# grab.net
KiCad netlist of a schematic drawn in EAGLE
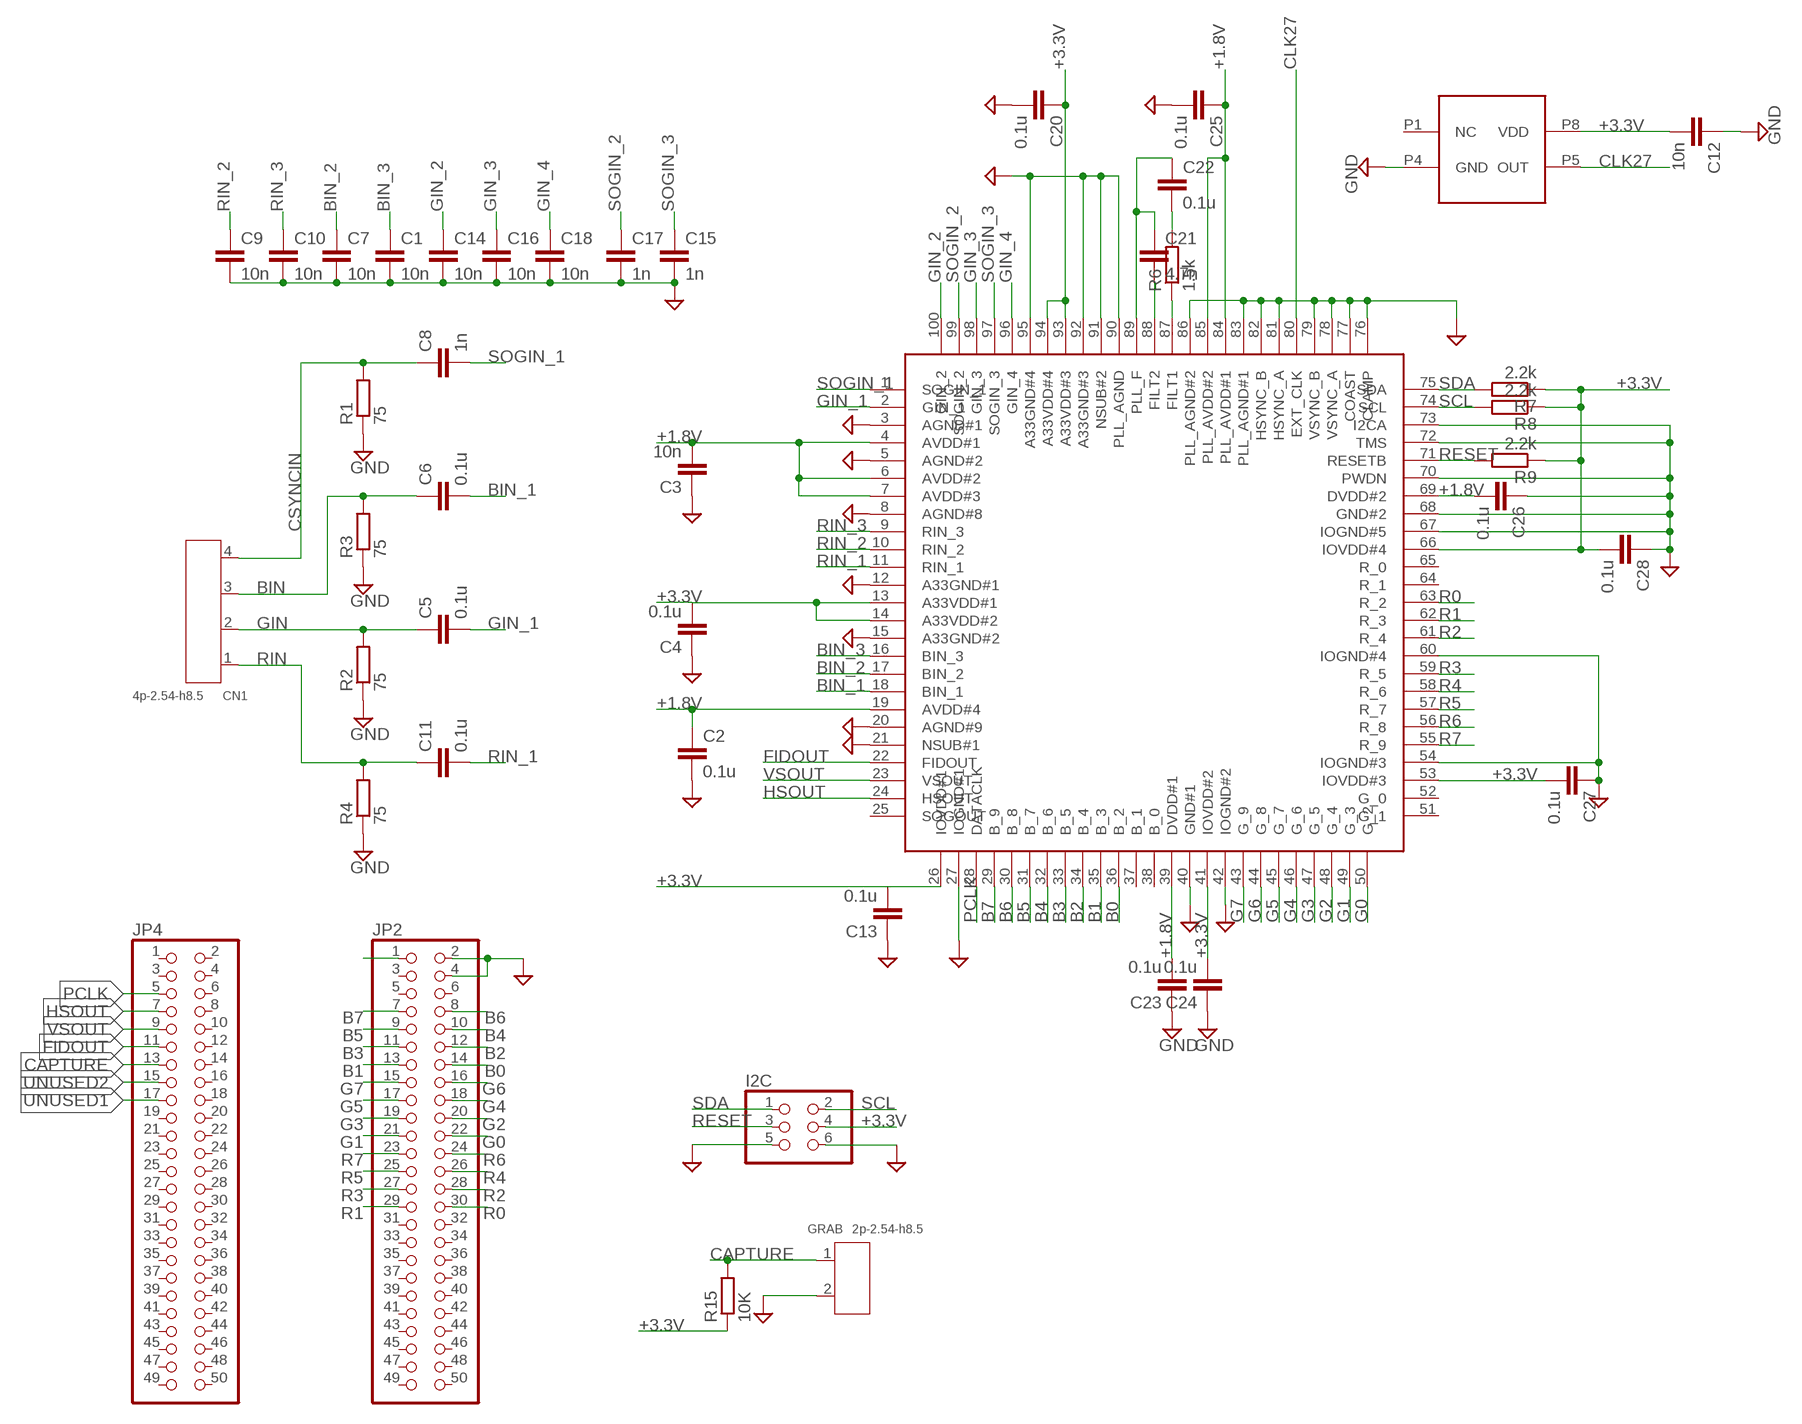
[diagram p0: schematic, sheet 1]
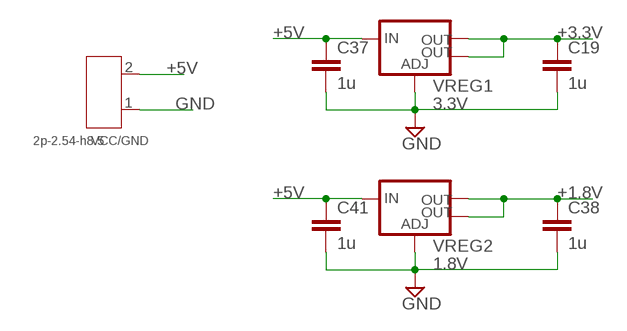
[diagram p1: schematic, sheet 2]
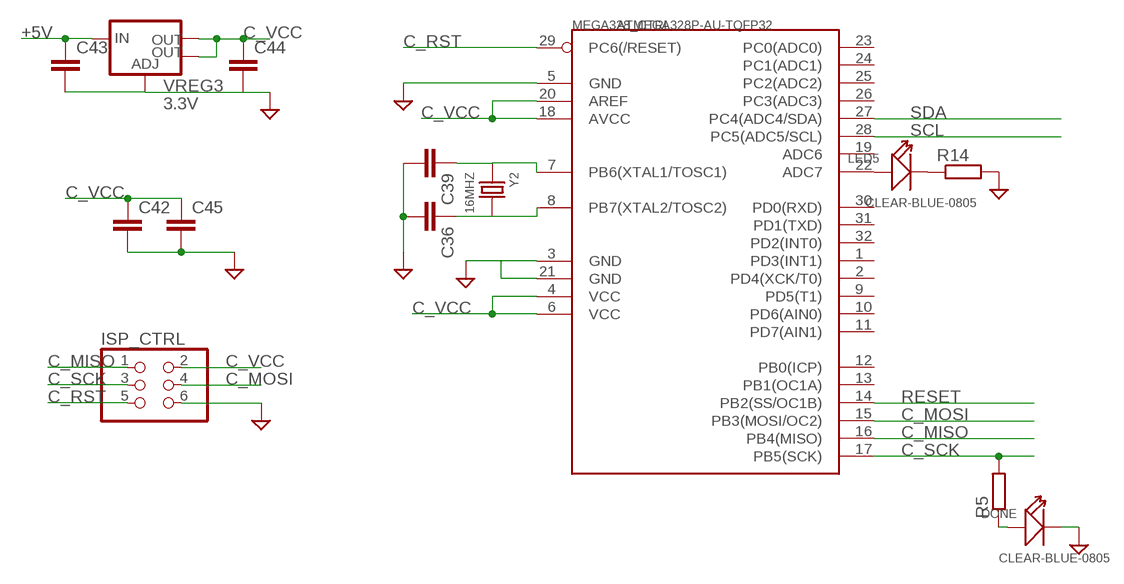
[diagram p2: schematic, sheet 3]
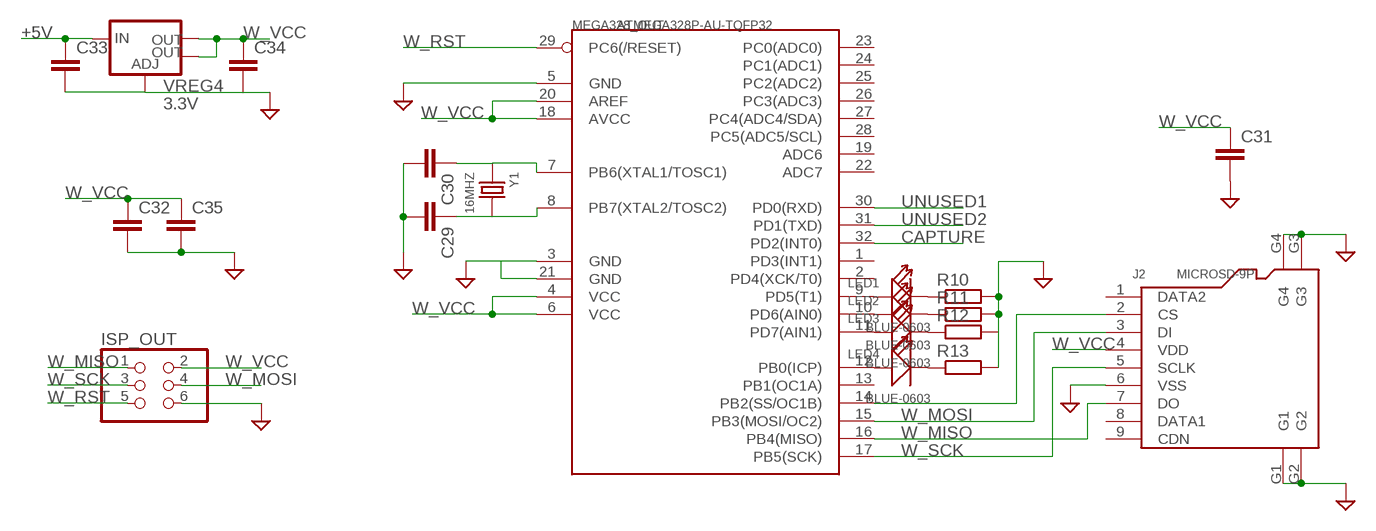
[diagram p3: schematic, sheet 4]

(export (version "E")
  (design (tool "Eeschema 10.0.6"))
  (components
    (comp (ref "C19")
      (value "1u")
      (footprint "eagle-import:C0603")
      (libsource (lib "eagle-import") (part "resistor_C-EUC0603"))
    )
    (comp (ref "C37")
      (value "1u")
      (footprint "eagle-import:C0603")
      (libsource (lib "eagle-import") (part "resistor_C-EUC0603"))
    )
    (comp (ref "C38")
      (value "1u")
      (footprint "eagle-import:C0603")
      (libsource (lib "eagle-import") (part "resistor_C-EUC0603"))
    )
    (comp (ref "C41")
      (value "1u")
      (footprint "eagle-import:C0603")
      (libsource (lib "eagle-import") (part "resistor_C-EUC0603"))
    )
    (comp (ref "VCC/GND")
      (value "2p-2.54-h8.5")
      (footprint "eagle-import:H2-2.54-3.44X6.3MM")
      (fields (field (name "MPN") "GS019-2.54-2P-1"))
      (libsource (lib "eagle-import") (part "DIP-SCREW-TERMINAL-GREEN(2P-2.54-H8.5)"))
    )
    (comp (ref "VREG1")
      (value "3.3V")
      (footprint "eagle-import:SOT223")
      (libsource (lib "eagle-import") (part "V_REG_LM1117SOT223"))
    )
    (comp (ref "VREG2")
      (value "1.8V")
      (footprint "eagle-import:SOT223")
      (libsource (lib "eagle-import") (part "V_REG_LM1117SOT223"))
    )
    (comp (ref "C36")
      (value "C-EUC0603")
      (footprint "eagle-import:C0603")
      (libsource (lib "eagle-import") (part "resistor_C-EUC0603"))
    )
    (comp (ref "C39")
      (value "C-EUC0603")
      (footprint "eagle-import:C0603")
      (libsource (lib "eagle-import") (part "resistor_C-EUC0603"))
    )
    (comp (ref "C42")
      (value "C-EUC0603")
      (footprint "eagle-import:C0603")
      (libsource (lib "eagle-import") (part "resistor_C-EUC0603"))
    )
    (comp (ref "C43")
      (value "C-EUC0603")
      (footprint "eagle-import:C0603")
      (libsource (lib "eagle-import") (part "resistor_C-EUC0603"))
    )
    (comp (ref "C44")
      (value "C-EUC0603")
      (footprint "eagle-import:C0603")
      (libsource (lib "eagle-import") (part "resistor_C-EUC0603"))
    )
    (comp (ref "C45")
      (value "C-EUC0603")
      (footprint "eagle-import:C0603")
      (libsource (lib "eagle-import") (part "resistor_C-EUC0603"))
    )
    (comp (ref "DONE")
      (value "CLEAR-BLUE-0805")
      (footprint "eagle-import:LED-0805")
      (fields (field (name "MPN") "EL-17-215/BHC-AN1P2/3T"))
      (libsource (lib "eagle-import") (part "SMD-LED-CLEAR-BLUE(0805)"))
    )
    (comp (ref "ISP_CTRL")
      (value "PINHD-2X3")
      (footprint "eagle-import:2X03")
      (libsource (lib "eagle-import") (part "PINHD-2X3"))
    )
    (comp (ref "LED5")
      (value "CLEAR-BLUE-0805")
      (footprint "eagle-import:LED-0805")
      (fields (field (name "MPN") "EL-17-215/BHC-AN1P2/3T"))
      (libsource (lib "eagle-import") (part "SMD-LED-CLEAR-BLUE(0805)"))
    )
    (comp (ref "MEGA328_CTRL")
      (value "ATMEGA328P-AU-TQFP32")
      (footprint "eagle-import:TQFP32-0.8-7X7MM")
      (fields (field (name "MPN") "ATMEGA328P-AU"))
      (libsource (lib "eagle-import") (part "MCU-ATMEGA328P-AU(TQFP32)"))
    )
    (comp (ref "R5")
      (value "R-EU_R0603")
      (footprint "eagle-import:R0603")
      (libsource (lib "eagle-import") (part "R-EU_R0603"))
    )
    (comp (ref "R14")
      (value "R-EU_R0603")
      (footprint "eagle-import:R0603")
      (libsource (lib "eagle-import") (part "R-EU_R0603"))
    )
    (comp (ref "VREG3")
      (value "3.3V")
      (footprint "eagle-import:SOT223")
      (libsource (lib "eagle-import") (part "V_REG_LM1117SOT223"))
    )
    (comp (ref "Y2")
      (value "16MHZ")
      (footprint "eagle-import:X2-SMD-5.0X3.2X1.3MM")
      (fields (field (name "MPN") "X053201602002"))
      (libsource (lib "eagle-import") (part "SMD-CRYSTAL-16MHZ-8PF-20PPM-40R(2P-5.0X3.2MM)"))
    )
    (comp (ref "C29")
      (value "C-EUC0603")
      (footprint "eagle-import:C0603")
      (libsource (lib "eagle-import") (part "resistor_C-EUC0603"))
    )
    (comp (ref "C30")
      (value "C-EUC0603")
      (footprint "eagle-import:C0603")
      (libsource (lib "eagle-import") (part "resistor_C-EUC0603"))
    )
    (comp (ref "C31")
      (value "C-EUC0603")
      (footprint "eagle-import:C0603")
      (libsource (lib "eagle-import") (part "resistor_C-EUC0603"))
    )
    (comp (ref "C32")
      (value "C-EUC0603")
      (footprint "eagle-import:C0603")
      (libsource (lib "eagle-import") (part "resistor_C-EUC0603"))
    )
    (comp (ref "C33")
      (value "C-EUC0603")
      (footprint "eagle-import:C0603")
      (libsource (lib "eagle-import") (part "resistor_C-EUC0603"))
    )
    (comp (ref "C34")
      (value "C-EUC0603")
      (footprint "eagle-import:C0603")
      (libsource (lib "eagle-import") (part "resistor_C-EUC0603"))
    )
    (comp (ref "C35")
      (value "C-EUC0603")
      (footprint "eagle-import:C0603")
      (libsource (lib "eagle-import") (part "resistor_C-EUC0603"))
    )
    (comp (ref "ISP_OUT")
      (value "PINHD-2X3")
      (footprint "eagle-import:2X03")
      (libsource (lib "eagle-import") (part "PINHD-2X3"))
    )
    (comp (ref "J2")
      (value "MICROSD-9P")
      (footprint "eagle-import:MICRO-SD9+4P-SMD-16.1X14.5X1.85MM")
      (libsource (lib "eagle-import") (part "MICRO-SD-CARD-HOLDER-9P"))
    )
    (comp (ref "LED1")
      (value "BLUE-0603")
      (footprint "eagle-import:LED-0603")
      (fields (field (name "MPN") "19-217-BHC-ZL1M2RY-3T"))
      (libsource (lib "eagle-import") (part "SMD-LED-CLEAR-BLUE(0603)"))
    )
    (comp (ref "LED2")
      (value "BLUE-0603")
      (footprint "eagle-import:LED-0603")
      (fields (field (name "MPN") "19-217-BHC-ZL1M2RY-3T"))
      (libsource (lib "eagle-import") (part "SMD-LED-CLEAR-BLUE(0603)"))
    )
    (comp (ref "LED3")
      (value "BLUE-0603")
      (footprint "eagle-import:LED-0603")
      (fields (field (name "MPN") "19-217-BHC-ZL1M2RY-3T"))
      (libsource (lib "eagle-import") (part "SMD-LED-CLEAR-BLUE(0603)"))
    )
    (comp (ref "LED4")
      (value "BLUE-0603")
      (footprint "eagle-import:LED-0603")
      (fields (field (name "MPN") "19-217-BHC-ZL1M2RY-3T"))
      (libsource (lib "eagle-import") (part "SMD-LED-CLEAR-BLUE(0603)"))
    )
    (comp (ref "MEGA328_OUT")
      (value "ATMEGA328P-AU-TQFP32")
      (footprint "eagle-import:TQFP32-0.8-7X7MM")
      (fields (field (name "MPN") "ATMEGA328P-AU"))
      (libsource (lib "eagle-import") (part "MCU-ATMEGA328P-AU(TQFP32)"))
    )
    (comp (ref "R10")
      (value "R-EU_R0603")
      (footprint "eagle-import:R0603")
      (libsource (lib "eagle-import") (part "R-EU_R0603"))
    )
    (comp (ref "R11")
      (value "R-EU_R0603")
      (footprint "eagle-import:R0603")
      (libsource (lib "eagle-import") (part "R-EU_R0603"))
    )
    (comp (ref "R12")
      (value "R-EU_R0603")
      (footprint "eagle-import:R0603")
      (libsource (lib "eagle-import") (part "R-EU_R0603"))
    )
    (comp (ref "R13")
      (value "R-EU_R0603")
      (footprint "eagle-import:R0603")
      (libsource (lib "eagle-import") (part "R-EU_R0603"))
    )
    (comp (ref "VREG4")
      (value "3.3V")
      (footprint "eagle-import:SOT223")
      (libsource (lib "eagle-import") (part "V_REG_LM1117SOT223"))
    )
    (comp (ref "Y1")
      (value "16MHZ")
      (footprint "eagle-import:X2-SMD-5.0X3.2X1.3MM")
      (fields (field (name "MPN") "X053201602002"))
      (libsource (lib "eagle-import") (part "SMD-CRYSTAL-16MHZ-8PF-20PPM-40R(2P-5.0X3.2MM)"))
    )
    (comp (ref "27MHZ")
      (value "ACHL-27MHZ-EK")
      (footprint "eagle-import:DIP4")
      (libsource (lib "eagle-import") (part "ACHL-27MHZ-EK"))
    )
    (comp (ref "C1")
      (value "10n")
      (footprint "eagle-import:C0603")
      (libsource (lib "eagle-import") (part "resistor_C-EUC0603"))
    )
    (comp (ref "C2")
      (value "0.1u")
      (footprint "eagle-import:C0603")
      (libsource (lib "eagle-import") (part "resistor_C-EUC0603"))
    )
    (comp (ref "C3")
      (value "10n")
      (footprint "eagle-import:C0603")
      (libsource (lib "eagle-import") (part "resistor_C-EUC0603"))
    )
    (comp (ref "C4")
      (value "0.1u")
      (footprint "eagle-import:C0603")
      (libsource (lib "eagle-import") (part "resistor_C-EUC0603"))
    )
    (comp (ref "C5")
      (value "0.1u")
      (footprint "eagle-import:C0603")
      (libsource (lib "eagle-import") (part "resistor_C-EUC0603"))
    )
    (comp (ref "C6")
      (value "0.1u")
      (footprint "eagle-import:C0603")
      (libsource (lib "eagle-import") (part "resistor_C-EUC0603"))
    )
    (comp (ref "C7")
      (value "10n")
      (footprint "eagle-import:C0603")
      (libsource (lib "eagle-import") (part "resistor_C-EUC0603"))
    )
    (comp (ref "C8")
      (value "1n")
      (footprint "eagle-import:C0603")
      (libsource (lib "eagle-import") (part "resistor_C-EUC0603"))
    )
    (comp (ref "C9")
      (value "10n")
      (footprint "eagle-import:C0603")
      (libsource (lib "eagle-import") (part "resistor_C-EUC0603"))
    )
    (comp (ref "C10")
      (value "10n")
      (footprint "eagle-import:C0603")
      (libsource (lib "eagle-import") (part "resistor_C-EUC0603"))
    )
    (comp (ref "C11")
      (value "0.1u")
      (footprint "eagle-import:C0603")
      (libsource (lib "eagle-import") (part "resistor_C-EUC0603"))
    )
    (comp (ref "C12")
      (value "10n")
      (footprint "eagle-import:C0805")
      (libsource (lib "eagle-import") (part "C-EUC0805"))
    )
    (comp (ref "C13")
      (value "0.1u")
      (footprint "eagle-import:C0603")
      (libsource (lib "eagle-import") (part "resistor_C-EUC0603"))
    )
    (comp (ref "C14")
      (value "10n")
      (footprint "eagle-import:C0603")
      (libsource (lib "eagle-import") (part "resistor_C-EUC0603"))
    )
    (comp (ref "C15")
      (value "1n")
      (footprint "eagle-import:C0603")
      (libsource (lib "eagle-import") (part "resistor_C-EUC0603"))
    )
    (comp (ref "C16")
      (value "10n")
      (footprint "eagle-import:C0603")
      (libsource (lib "eagle-import") (part "resistor_C-EUC0603"))
    )
    (comp (ref "C17")
      (value "1n")
      (footprint "eagle-import:C0603")
      (libsource (lib "eagle-import") (part "resistor_C-EUC0603"))
    )
    (comp (ref "C18")
      (value "10n")
      (footprint "eagle-import:C0603")
      (libsource (lib "eagle-import") (part "resistor_C-EUC0603"))
    )
    (comp (ref "C20")
      (value "0.1u")
      (footprint "eagle-import:C0603")
      (libsource (lib "eagle-import") (part "resistor_C-EUC0603"))
    )
    (comp (ref "C21")
      (value "4.7n")
      (footprint "eagle-import:C0603")
      (libsource (lib "eagle-import") (part "resistor_C-EUC0603"))
    )
    (comp (ref "C22")
      (value "0.1u")
      (footprint "eagle-import:C0603")
      (libsource (lib "eagle-import") (part "resistor_C-EUC0603"))
    )
    (comp (ref "C23")
      (value "0.1u")
      (footprint "eagle-import:C0603")
      (libsource (lib "eagle-import") (part "resistor_C-EUC0603"))
    )
    (comp (ref "C24")
      (value "0.1u")
      (footprint "eagle-import:C0603")
      (libsource (lib "eagle-import") (part "resistor_C-EUC0603"))
    )
    (comp (ref "C25")
      (value "0.1u")
      (footprint "eagle-import:C0603")
      (libsource (lib "eagle-import") (part "resistor_C-EUC0603"))
    )
    (comp (ref "C26")
      (value "0.1u")
      (footprint "eagle-import:C0603")
      (libsource (lib "eagle-import") (part "resistor_C-EUC0603"))
    )
    (comp (ref "C27")
      (value "0.1u")
      (footprint "eagle-import:C0603")
      (libsource (lib "eagle-import") (part "resistor_C-EUC0603"))
    )
    (comp (ref "C28")
      (value "0.1u")
      (footprint "eagle-import:C0603")
      (libsource (lib "eagle-import") (part "resistor_C-EUC0603"))
    )
    (comp (ref "CN1")
      (value "4p-2.54-h8.5")
      (footprint "eagle-import:H4-2.54-8.52X6.3MM")
      (fields (field (name "MPN") "GS019-2.54-4P-1"))
      (libsource (lib "eagle-import") (part "DIP-SCREW-TERMINAL-GREEN(4P-2.54-H8.5)"))
    )
    (comp (ref "GRAB")
      (value "2p-2.54-h8.5")
      (footprint "eagle-import:H2-2.54-3.44X6.3MM")
      (fields (field (name "MPN") "GS019-2.54-2P-1"))
      (libsource (lib "eagle-import") (part "DIP-SCREW-TERMINAL-GREEN(2P-2.54-H8.5)"))
    )
    (comp (ref "I2C")
      (value "PINHD-2X3")
      (footprint "eagle-import:2X03")
      (libsource (lib "eagle-import") (part "PINHD-2X3"))
    )
    (comp (ref "JP2")
      (value "PINHD-2X25")
      (footprint "eagle-import:2X25")
      (libsource (lib "eagle-import") (part "PINHD-2X25"))
    )
    (comp (ref "JP4")
      (value "PINHD-2X25")
      (footprint "eagle-import:2X25")
      (libsource (lib "eagle-import") (part "PINHD-2X25"))
    )
    (comp (ref "R1")
      (value "75")
      (footprint "eagle-import:R0603")
      (libsource (lib "eagle-import") (part "R-EU_R0603"))
    )
    (comp (ref "R2")
      (value "75")
      (footprint "eagle-import:R0603")
      (libsource (lib "eagle-import") (part "R-EU_R0603"))
    )
    (comp (ref "R3")
      (value "75")
      (footprint "eagle-import:R0603")
      (libsource (lib "eagle-import") (part "R-EU_R0603"))
    )
    (comp (ref "R4")
      (value "75")
      (footprint "eagle-import:R0603")
      (libsource (lib "eagle-import") (part "R-EU_R0603"))
    )
    (comp (ref "R6")
      (value "1.5k")
      (footprint "eagle-import:R0603")
      (libsource (lib "eagle-import") (part "R-EU_R0603"))
    )
    (comp (ref "R7")
      (value "2.2k")
      (footprint "eagle-import:R0603")
      (libsource (lib "eagle-import") (part "R-EU_R0603"))
    )
    (comp (ref "R8")
      (value "2.2k")
      (footprint "eagle-import:R0603")
      (libsource (lib "eagle-import") (part "R-EU_R0603"))
    )
    (comp (ref "R9")
      (value "2.2k")
      (footprint "eagle-import:R0603")
      (libsource (lib "eagle-import") (part "R-EU_R0603"))
    )
    (comp (ref "R15")
      (value "10K")
      (footprint "eagle-import:R0603")
      (libsource (lib "eagle-import") (part "R-EU_R0603"))
    )
    (comp (ref "TVP7002")
      (value "TVP7002")
      (footprint "eagle-import:TQFP100")
      (libsource (lib "eagle-import") (part "TVP7002"))
    )
  )
  (nets
    (net (code "1") (name "+1.8V") (class "Default")
      (node (ref "C2") (pin "1") (pinfunction "1_1") (pintype "passive"))
      (node (ref "C23") (pin "2") (pinfunction "2_2") (pintype "passive"))
      (node (ref "C25") (pin "1") (pinfunction "1_1") (pintype "passive"))
      (node (ref "C26") (pin "2") (pinfunction "2_2") (pintype "passive"))
      (node (ref "C3") (pin "2") (pinfunction "2_2") (pintype "passive"))
      (node (ref "C38") (pin "1") (pinfunction "1_1") (pintype "passive"))
      (node (ref "TVP7002") (pin "19") (pinfunction "AVDD#4_19") (pintype "bidirectional"))
      (node (ref "TVP7002") (pin "39") (pinfunction "DVDD#1_39") (pintype "bidirectional"))
      (node (ref "TVP7002") (pin "4") (pinfunction "AVDD#1_4") (pintype "bidirectional"))
      (node (ref "TVP7002") (pin "6") (pinfunction "AVDD#2_6") (pintype "bidirectional"))
      (node (ref "TVP7002") (pin "69") (pinfunction "DVDD#2_69") (pintype "bidirectional"))
      (node (ref "TVP7002") (pin "7") (pinfunction "AVDD#3_7") (pintype "bidirectional"))
      (node (ref "TVP7002") (pin "84") (pinfunction "PLL_AVDD#1_84") (pintype "bidirectional"))
      (node (ref "TVP7002") (pin "85") (pinfunction "PLL_AVDD#2_85") (pintype "bidirectional"))
      (node (ref "VREG2") (pin "2") (pinfunction "OUT_2") (pintype "output"))
      (node (ref "VREG2") (pin "4") (pinfunction "OUT_4") (pintype "output"))
    )
    (net (code "2") (name "+3.3V") (class "Default")
      (node (ref "27MHZ") (pin "P8") (pinfunction "VDD_P8") (pintype "bidirectional"))
      (node (ref "C12") (pin "2") (pinfunction "2_2") (pintype "passive"))
      (node (ref "C13") (pin "2") (pinfunction "2_2") (pintype "passive"))
      (node (ref "C19") (pin "1") (pinfunction "1_1") (pintype "passive"))
      (node (ref "C20") (pin "1") (pinfunction "1_1") (pintype "passive"))
      (node (ref "C24") (pin "2") (pinfunction "2_2") (pintype "passive"))
      (node (ref "C27") (pin "2") (pinfunction "2_2") (pintype "passive"))
      (node (ref "C28") (pin "2") (pinfunction "2_2") (pintype "passive"))
      (node (ref "C4") (pin "2") (pinfunction "2_2") (pintype "passive"))
      (node (ref "I2C") (pin "4") (pinfunction "4_4") (pintype "passive"))
      (node (ref "R15") (pin "1") (pinfunction "1_1") (pintype "passive"))
      (node (ref "R7") (pin "1") (pinfunction "1_1") (pintype "passive"))
      (node (ref "R8") (pin "1") (pinfunction "1_1") (pintype "passive"))
      (node (ref "R9") (pin "1") (pinfunction "1_1") (pintype "passive"))
      (node (ref "TVP7002") (pin "13") (pinfunction "A33VDD#1_13") (pintype "bidirectional"))
      (node (ref "TVP7002") (pin "14") (pinfunction "A33VDD#2_14") (pintype "bidirectional"))
      (node (ref "TVP7002") (pin "26") (pinfunction "IOVDD#1_26") (pintype "bidirectional"))
      (node (ref "TVP7002") (pin "41") (pinfunction "IOVDD#2_41") (pintype "bidirectional"))
      (node (ref "TVP7002") (pin "53") (pinfunction "IOVDD#3_53") (pintype "bidirectional"))
      (node (ref "TVP7002") (pin "66") (pinfunction "IOVDD#4_66") (pintype "bidirectional"))
      (node (ref "TVP7002") (pin "93") (pinfunction "A33VDD#3_93") (pintype "bidirectional"))
      (node (ref "TVP7002") (pin "94") (pinfunction "A33VDD#4_94") (pintype "bidirectional"))
      (node (ref "VREG1") (pin "2") (pinfunction "OUT_2") (pintype "output"))
      (node (ref "VREG1") (pin "4") (pinfunction "OUT_4") (pintype "output"))
    )
    (net (code "3") (name "+5V") (class "Default")
      (node (ref "C33") (pin "1") (pinfunction "1_1") (pintype "passive"))
      (node (ref "C37") (pin "1") (pinfunction "1_1") (pintype "passive"))
      (node (ref "C41") (pin "1") (pinfunction "1_1") (pintype "passive"))
      (node (ref "C43") (pin "1") (pinfunction "1_1") (pintype "passive"))
      (node (ref "VCC/GND") (pin "2") (pinfunction "2_2") (pintype "bidirectional"))
      (node (ref "VREG1") (pin "3") (pinfunction "IN_3") (pintype "input"))
      (node (ref "VREG2") (pin "3") (pinfunction "IN_3") (pintype "input"))
      (node (ref "VREG3") (pin "3") (pinfunction "IN_3") (pintype "input"))
      (node (ref "VREG4") (pin "3") (pinfunction "IN_3") (pintype "input"))
    )
    (net (code "4") (name "B0") (class "Default")
      (node (ref "JP2") (pin "14") (pinfunction "14_14") (pintype "passive"))
      (node (ref "TVP7002") (pin "36") (pinfunction "B_2_36") (pintype "bidirectional"))
    )
    (net (code "5") (name "B1") (class "Default")
      (node (ref "JP2") (pin "13") (pinfunction "13_13") (pintype "passive"))
      (node (ref "TVP7002") (pin "35") (pinfunction "B_3_35") (pintype "bidirectional"))
    )
    (net (code "6") (name "B2") (class "Default")
      (node (ref "JP2") (pin "12") (pinfunction "12_12") (pintype "passive"))
      (node (ref "TVP7002") (pin "34") (pinfunction "B_4_34") (pintype "bidirectional"))
    )
    (net (code "7") (name "B3") (class "Default")
      (node (ref "JP2") (pin "11") (pinfunction "11_11") (pintype "passive"))
      (node (ref "TVP7002") (pin "33") (pinfunction "B_5_33") (pintype "bidirectional"))
    )
    (net (code "8") (name "B4") (class "Default")
      (node (ref "JP2") (pin "10") (pinfunction "10_10") (pintype "passive"))
      (node (ref "TVP7002") (pin "32") (pinfunction "B_6_32") (pintype "bidirectional"))
    )
    (net (code "9") (name "B5") (class "Default")
      (node (ref "JP2") (pin "9") (pinfunction "9_9") (pintype "passive"))
      (node (ref "TVP7002") (pin "31") (pinfunction "B_7_31") (pintype "bidirectional"))
    )
    (net (code "10") (name "B6") (class "Default")
      (node (ref "JP2") (pin "8") (pinfunction "8_8") (pintype "passive"))
      (node (ref "TVP7002") (pin "30") (pinfunction "B_8_30") (pintype "bidirectional"))
    )
    (net (code "11") (name "B7") (class "Default")
      (node (ref "JP2") (pin "7") (pinfunction "7_7") (pintype "passive"))
      (node (ref "TVP7002") (pin "29") (pinfunction "B_9_29") (pintype "bidirectional"))
    )
    (net (code "12") (name "BIN") (class "Default")
      (node (ref "C6") (pin "1") (pinfunction "1_1") (pintype "passive"))
      (node (ref "CN1") (pin "3") (pinfunction "3_3") (pintype "bidirectional"))
      (node (ref "R3") (pin "2") (pinfunction "2_2") (pintype "passive"))
    )
    (net (code "13") (name "BIN_1") (class "Default")
      (node (ref "C6") (pin "2") (pinfunction "2_2") (pintype "passive"))
      (node (ref "TVP7002") (pin "18") (pinfunction "BIN_1_18") (pintype "bidirectional"))
    )
    (net (code "14") (name "BIN_2") (class "Default")
      (node (ref "C7") (pin "1") (pinfunction "1_1") (pintype "passive"))
      (node (ref "TVP7002") (pin "17") (pinfunction "BIN_2_17") (pintype "bidirectional"))
    )
    (net (code "15") (name "BIN_3") (class "Default")
      (node (ref "C1") (pin "1") (pinfunction "1_1") (pintype "passive"))
      (node (ref "TVP7002") (pin "16") (pinfunction "BIN_3_16") (pintype "bidirectional"))
    )
    (net (code "16") (name "CAPTURE") (class "Default")
      (node (ref "GRAB") (pin "1") (pinfunction "1_1") (pintype "bidirectional"))
      (node (ref "JP4") (pin "13") (pinfunction "13_13") (pintype "passive"))
      (node (ref "MEGA328_OUT") (pin "32") (pinfunction "PD2(INT0)_32") (pintype "bidirectional"))
      (node (ref "R15") (pin "2") (pinfunction "2_2") (pintype "passive"))
    )
    (net (code "17") (name "CLK27") (class "Default")
      (node (ref "27MHZ") (pin "P5") (pinfunction "OUT_P5") (pintype "bidirectional"))
      (node (ref "TVP7002") (pin "80") (pinfunction "EXT_CLK_80") (pintype "bidirectional"))
    )
    (net (code "18") (name "CSYNCIN") (class "Default")
      (node (ref "C8") (pin "1") (pinfunction "1_1") (pintype "passive"))
      (node (ref "CN1") (pin "4") (pinfunction "4_4") (pintype "bidirectional"))
      (node (ref "R1") (pin "2") (pinfunction "2_2") (pintype "passive"))
    )
    (net (code "19") (name "C_MISO") (class "Default")
      (node (ref "ISP_CTRL") (pin "1") (pinfunction "1_1") (pintype "passive"))
      (node (ref "MEGA328_CTRL") (pin "16") (pinfunction "PB4(MISO)_16") (pintype "bidirectional"))
    )
    (net (code "20") (name "C_MOSI") (class "Default")
      (node (ref "ISP_CTRL") (pin "4") (pinfunction "4_4") (pintype "passive"))
      (node (ref "MEGA328_CTRL") (pin "15") (pinfunction "PB3(MOSI/OC2)_15") (pintype "bidirectional"))
    )
    (net (code "21") (name "C_RST") (class "Default")
      (node (ref "ISP_CTRL") (pin "5") (pinfunction "5_5") (pintype "passive"))
      (node (ref "MEGA328_CTRL") (pin "29") (pinfunction "PC6(/RESET)_29") (pintype "bidirectional"))
    )
    (net (code "22") (name "C_SCK") (class "Default")
      (node (ref "ISP_CTRL") (pin "3") (pinfunction "3_3") (pintype "passive"))
      (node (ref "MEGA328_CTRL") (pin "17") (pinfunction "PB5(SCK)_17") (pintype "bidirectional"))
      (node (ref "R5") (pin "2") (pinfunction "2_2") (pintype "passive"))
    )
    (net (code "23") (name "C_VCC") (class "Default")
      (node (ref "C42") (pin "1") (pinfunction "1_1") (pintype "passive"))
      (node (ref "C44") (pin "1") (pinfunction "1_1") (pintype "passive"))
      (node (ref "C45") (pin "1") (pinfunction "1_1") (pintype "passive"))
      (node (ref "ISP_CTRL") (pin "2") (pinfunction "2_2") (pintype "passive"))
      (node (ref "MEGA328_CTRL") (pin "18") (pinfunction "AVCC_18") (pintype "bidirectional"))
      (node (ref "MEGA328_CTRL") (pin "20") (pinfunction "AREF_20") (pintype "bidirectional"))
      (node (ref "MEGA328_CTRL") (pin "4") (pinfunction "VCC_4") (pintype "bidirectional"))
      (node (ref "MEGA328_CTRL") (pin "6") (pinfunction "VCC_6") (pintype "bidirectional"))
      (node (ref "VREG3") (pin "2") (pinfunction "OUT_2") (pintype "output"))
      (node (ref "VREG3") (pin "4") (pinfunction "OUT_4") (pintype "output"))
    )
    (net (code "24") (name "FIDOUT") (class "Default")
      (node (ref "JP4") (pin "11") (pinfunction "11_11") (pintype "passive"))
      (node (ref "TVP7002") (pin "22") (pinfunction "FIDOUT_22") (pintype "bidirectional"))
    )
    (net (code "25") (name "G0") (class "Default")
      (node (ref "JP2") (pin "22") (pinfunction "22_22") (pintype "passive"))
      (node (ref "TVP7002") (pin "50") (pinfunction "G_2_50") (pintype "bidirectional"))
    )
    (net (code "26") (name "G1") (class "Default")
      (node (ref "JP2") (pin "21") (pinfunction "21_21") (pintype "passive"))
      (node (ref "TVP7002") (pin "49") (pinfunction "G_3_49") (pintype "bidirectional"))
    )
    (net (code "27") (name "G2") (class "Default")
      (node (ref "JP2") (pin "20") (pinfunction "20_20") (pintype "passive"))
      (node (ref "TVP7002") (pin "48") (pinfunction "G_4_48") (pintype "bidirectional"))
    )
    (net (code "28") (name "G3") (class "Default")
      (node (ref "JP2") (pin "19") (pinfunction "19_19") (pintype "passive"))
      (node (ref "TVP7002") (pin "47") (pinfunction "G_5_47") (pintype "bidirectional"))
    )
    (net (code "29") (name "G4") (class "Default")
      (node (ref "JP2") (pin "18") (pinfunction "18_18") (pintype "passive"))
      (node (ref "TVP7002") (pin "46") (pinfunction "G_6_46") (pintype "bidirectional"))
    )
    (net (code "30") (name "G5") (class "Default")
      (node (ref "JP2") (pin "17") (pinfunction "17_17") (pintype "passive"))
      (node (ref "TVP7002") (pin "45") (pinfunction "G_7_45") (pintype "bidirectional"))
    )
    (net (code "31") (name "G6") (class "Default")
      (node (ref "JP2") (pin "16") (pinfunction "16_16") (pintype "passive"))
      (node (ref "TVP7002") (pin "44") (pinfunction "G_8_44") (pintype "bidirectional"))
    )
    (net (code "32") (name "G7") (class "Default")
      (node (ref "JP2") (pin "15") (pinfunction "15_15") (pintype "passive"))
      (node (ref "TVP7002") (pin "43") (pinfunction "G_9_43") (pintype "bidirectional"))
    )
    (net (code "33") (name "GIN") (class "Default")
      (node (ref "C5") (pin "1") (pinfunction "1_1") (pintype "passive"))
      (node (ref "CN1") (pin "2") (pinfunction "2_2") (pintype "bidirectional"))
      (node (ref "R2") (pin "2") (pinfunction "2_2") (pintype "passive"))
    )
    (net (code "34") (name "GIN_1") (class "Default")
      (node (ref "C5") (pin "2") (pinfunction "2_2") (pintype "passive"))
      (node (ref "TVP7002") (pin "2") (pinfunction "GIN_1_2") (pintype "bidirectional"))
    )
    (net (code "35") (name "GIN_2") (class "Default")
      (node (ref "C14") (pin "1") (pinfunction "1_1") (pintype "passive"))
      (node (ref "TVP7002") (pin "100") (pinfunction "GIN_2_100") (pintype "bidirectional"))
    )
    (net (code "36") (name "GIN_3") (class "Default")
      (node (ref "C16") (pin "1") (pinfunction "1_1") (pintype "passive"))
      (node (ref "TVP7002") (pin "98") (pinfunction "GIN_3_98") (pintype "bidirectional"))
    )
    (net (code "37") (name "GIN_4") (class "Default")
      (node (ref "C18") (pin "1") (pinfunction "1_1") (pintype "passive"))
      (node (ref "TVP7002") (pin "96") (pinfunction "GIN_4_96") (pintype "bidirectional"))
    )
    (net (code "38") (name "GND") (class "Default")
      (node (ref "27MHZ") (pin "P4") (pinfunction "GND_P4") (pintype "bidirectional"))
      (node (ref "C1") (pin "2") (pinfunction "2_2") (pintype "passive"))
      (node (ref "C10") (pin "2") (pinfunction "2_2") (pintype "passive"))
      (node (ref "C12") (pin "1") (pinfunction "1_1") (pintype "passive"))
      (node (ref "C13") (pin "1") (pinfunction "1_1") (pintype "passive"))
      (node (ref "C14") (pin "2") (pinfunction "2_2") (pintype "passive"))
      (node (ref "C15") (pin "2") (pinfunction "2_2") (pintype "passive"))
      (node (ref "C16") (pin "2") (pinfunction "2_2") (pintype "passive"))
      (node (ref "C17") (pin "2") (pinfunction "2_2") (pintype "passive"))
      (node (ref "C18") (pin "2") (pinfunction "2_2") (pintype "passive"))
      (node (ref "C19") (pin "2") (pinfunction "2_2") (pintype "passive"))
      (node (ref "C2") (pin "2") (pinfunction "2_2") (pintype "passive"))
      (node (ref "C20") (pin "2") (pinfunction "2_2") (pintype "passive"))
      (node (ref "C23") (pin "1") (pinfunction "1_1") (pintype "passive"))
      (node (ref "C24") (pin "1") (pinfunction "1_1") (pintype "passive"))
      (node (ref "C25") (pin "2") (pinfunction "2_2") (pintype "passive"))
      (node (ref "C26") (pin "1") (pinfunction "1_1") (pintype "passive"))
      (node (ref "C27") (pin "1") (pinfunction "1_1") (pintype "passive"))
      (node (ref "C28") (pin "1") (pinfunction "1_1") (pintype "passive"))
      (node (ref "C29") (pin "2") (pinfunction "2_2") (pintype "passive"))
      (node (ref "C3") (pin "1") (pinfunction "1_1") (pintype "passive"))
      (node (ref "C30") (pin "2") (pinfunction "2_2") (pintype "passive"))
      (node (ref "C31") (pin "2") (pinfunction "2_2") (pintype "passive"))
      (node (ref "C32") (pin "2") (pinfunction "2_2") (pintype "passive"))
      (node (ref "C33") (pin "2") (pinfunction "2_2") (pintype "passive"))
      (node (ref "C34") (pin "2") (pinfunction "2_2") (pintype "passive"))
      (node (ref "C35") (pin "2") (pinfunction "2_2") (pintype "passive"))
      (node (ref "C36") (pin "2") (pinfunction "2_2") (pintype "passive"))
      (node (ref "C37") (pin "2") (pinfunction "2_2") (pintype "passive"))
      (node (ref "C38") (pin "2") (pinfunction "2_2") (pintype "passive"))
      (node (ref "C39") (pin "2") (pinfunction "2_2") (pintype "passive"))
      (node (ref "C4") (pin "1") (pinfunction "1_1") (pintype "passive"))
      (node (ref "C41") (pin "2") (pinfunction "2_2") (pintype "passive"))
      (node (ref "C42") (pin "2") (pinfunction "2_2") (pintype "passive"))
      (node (ref "C43") (pin "2") (pinfunction "2_2") (pintype "passive"))
      (node (ref "C44") (pin "2") (pinfunction "2_2") (pintype "passive"))
      (node (ref "C45") (pin "2") (pinfunction "2_2") (pintype "passive"))
      (node (ref "C7") (pin "2") (pinfunction "2_2") (pintype "passive"))
      (node (ref "C9") (pin "2") (pinfunction "2_2") (pintype "passive"))
      (node (ref "DONE") (pin "-") (pinfunction "-_-") (pintype "passive"))
      (node (ref "GRAB") (pin "2") (pinfunction "2_2") (pintype "bidirectional"))
      (node (ref "I2C") (pin "5") (pinfunction "5_5") (pintype "passive"))
      (node (ref "I2C") (pin "6") (pinfunction "6_6") (pintype "passive"))
      (node (ref "ISP_CTRL") (pin "6") (pinfunction "6_6") (pintype "passive"))
      (node (ref "ISP_OUT") (pin "6") (pinfunction "6_6") (pintype "passive"))
      (node (ref "J2") (pin "6") (pinfunction "VSS_6") (pintype "bidirectional"))
      (node (ref "J2") (pin "G1") (pinfunction "G1_G1") (pintype "bidirectional"))
      (node (ref "J2") (pin "G2") (pinfunction "G2_G2") (pintype "bidirectional"))
      (node (ref "J2") (pin "G3") (pinfunction "G3_G3") (pintype "bidirectional"))
      (node (ref "J2") (pin "G4") (pinfunction "G4_G4") (pintype "bidirectional"))
      (node (ref "JP2") (pin "2") (pinfunction "2_2") (pintype "passive"))
      (node (ref "JP2") (pin "4") (pinfunction "4_4") (pintype "passive"))
      (node (ref "MEGA328_CTRL") (pin "21") (pinfunction "GND_21") (pintype "bidirectional"))
      (node (ref "MEGA328_CTRL") (pin "3") (pinfunction "GND_3") (pintype "bidirectional"))
      (node (ref "MEGA328_CTRL") (pin "5") (pinfunction "GND_5") (pintype "bidirectional"))
      (node (ref "MEGA328_OUT") (pin "21") (pinfunction "GND_21") (pintype "bidirectional"))
      (node (ref "MEGA328_OUT") (pin "3") (pinfunction "GND_3") (pintype "bidirectional"))
      (node (ref "MEGA328_OUT") (pin "5") (pinfunction "GND_5") (pintype "bidirectional"))
      (node (ref "R1") (pin "1") (pinfunction "1_1") (pintype "passive"))
      (node (ref "R10") (pin "2") (pinfunction "2_2") (pintype "passive"))
      (node (ref "R11") (pin "2") (pinfunction "2_2") (pintype "passive"))
      (node (ref "R13") (pin "2") (pinfunction "2_2") (pintype "passive"))
      (node (ref "R14") (pin "2") (pinfunction "2_2") (pintype "passive"))
      (node (ref "R2") (pin "1") (pinfunction "1_1") (pintype "passive"))
      (node (ref "R3") (pin "1") (pinfunction "1_1") (pintype "passive"))
      (node (ref "R4") (pin "1") (pinfunction "1_1") (pintype "passive"))
      (node (ref "TVP7002") (pin "12") (pinfunction "A33GND#1_12") (pintype "bidirectional"))
      (node (ref "TVP7002") (pin "15") (pinfunction "A33GND#2_15") (pintype "bidirectional"))
      (node (ref "TVP7002") (pin "20") (pinfunction "AGND#9_20") (pintype "bidirectional"))
      (node (ref "TVP7002") (pin "21") (pinfunction "NSUB#1_21") (pintype "bidirectional"))
      (node (ref "TVP7002") (pin "27") (pinfunction "IOGND#1_27") (pintype "bidirectional"))
      (node (ref "TVP7002") (pin "3") (pinfunction "AGND#1_3") (pintype "bidirectional"))
      (node (ref "TVP7002") (pin "40") (pinfunction "GND#1_40") (pintype "bidirectional"))
      (node (ref "TVP7002") (pin "42") (pinfunction "IOGND#2_42") (pintype "bidirectional"))
      (node (ref "TVP7002") (pin "5") (pinfunction "AGND#2_5") (pintype "bidirectional"))
      (node (ref "TVP7002") (pin "54") (pinfunction "IOGND#3_54") (pintype "bidirectional"))
      (node (ref "TVP7002") (pin "60") (pinfunction "IOGND#4_60") (pintype "bidirectional"))
      (node (ref "TVP7002") (pin "67") (pinfunction "IOGND#5_67") (pintype "bidirectional"))
      (node (ref "TVP7002") (pin "68") (pinfunction "GND#2_68") (pintype "bidirectional"))
      (node (ref "TVP7002") (pin "70") (pinfunction "PWDN_70") (pintype "bidirectional"))
      (node (ref "TVP7002") (pin "72") (pinfunction "TMS_72") (pintype "bidirectional"))
      (node (ref "TVP7002") (pin "73") (pinfunction "I2CA_73") (pintype "bidirectional"))
      (node (ref "TVP7002") (pin "76") (pinfunction "CLAMP_76") (pintype "bidirectional"))
      (node (ref "TVP7002") (pin "77") (pinfunction "COAST_77") (pintype "bidirectional"))
      (node (ref "TVP7002") (pin "78") (pinfunction "VSYNC_A_78") (pintype "bidirectional"))
      (node (ref "TVP7002") (pin "79") (pinfunction "VSYNC_B_79") (pintype "bidirectional"))
      (node (ref "TVP7002") (pin "8") (pinfunction "AGND#8_8") (pintype "bidirectional"))
      (node (ref "TVP7002") (pin "81") (pinfunction "HSYNC_A_81") (pintype "bidirectional"))
      (node (ref "TVP7002") (pin "82") (pinfunction "HSYNC_B_82") (pintype "bidirectional"))
      (node (ref "TVP7002") (pin "83") (pinfunction "PLL_AGND#1_83") (pintype "bidirectional"))
      (node (ref "TVP7002") (pin "86") (pinfunction "PLL_AGND#2_86") (pintype "bidirectional"))
      (node (ref "TVP7002") (pin "90") (pinfunction "PLL_AGND_90") (pintype "bidirectional"))
      (node (ref "TVP7002") (pin "91") (pinfunction "NSUB#2_91") (pintype "bidirectional"))
      (node (ref "TVP7002") (pin "92") (pinfunction "A33GND#3_92") (pintype "bidirectional"))
      (node (ref "TVP7002") (pin "95") (pinfunction "A33GND#4_95") (pintype "bidirectional"))
      (node (ref "VCC/GND") (pin "1") (pinfunction "1_1") (pintype "bidirectional"))
      (node (ref "VREG1") (pin "1") (pinfunction "ADJ_1") (pintype "input"))
      (node (ref "VREG2") (pin "1") (pinfunction "ADJ_1") (pintype "input"))
      (node (ref "VREG3") (pin "1") (pinfunction "ADJ_1") (pintype "input"))
      (node (ref "VREG4") (pin "1") (pinfunction "ADJ_1") (pintype "input"))
    )
    (net (code "39") (name "HSOUT") (class "Default")
      (node (ref "JP4") (pin "7") (pinfunction "7_7") (pintype "passive"))
      (node (ref "TVP7002") (pin "24") (pinfunction "HSOUT_24") (pintype "bidirectional"))
    )
    (net (code "40") (name "Net-(C22-Pad2)") (class "Default")
      (node (ref "C22") (pin "2") (pinfunction "2_2") (pintype "passive"))
      (node (ref "R6") (pin "2") (pinfunction "2_2") (pintype "passive"))
    )
    (net (code "41") (name "Net-(DONE-Pad+)") (class "Default")
      (node (ref "DONE") (pin "+") (pinfunction "+_+") (pintype "passive"))
      (node (ref "R5") (pin "1") (pinfunction "1_1") (pintype "passive"))
    )
    (net (code "42") (name "Net-(J2-CS)") (class "Default")
      (node (ref "J2") (pin "2") (pinfunction "CS_2") (pintype "bidirectional"))
      (node (ref "MEGA328_OUT") (pin "14") (pinfunction "PB2(SS/OC1B)_14") (pintype "bidirectional"))
    )
    (net (code "43") (name "Net-(LED1-Pad-)") (class "Default")
      (node (ref "LED1") (pin "-") (pinfunction "-_-") (pintype "passive"))
      (node (ref "R10") (pin "1") (pinfunction "1_1") (pintype "passive"))
    )
    (net (code "44") (name "Net-(LED2-Pad-)") (class "Default")
      (node (ref "LED2") (pin "-") (pinfunction "-_-") (pintype "passive"))
      (node (ref "R11") (pin "1") (pinfunction "1_1") (pintype "passive"))
    )
    (net (code "45") (name "Net-(LED3-Pad-)") (class "Default")
      (node (ref "LED3") (pin "-") (pinfunction "-_-") (pintype "passive"))
      (node (ref "R12") (pin "1") (pinfunction "1_1") (pintype "passive"))
    )
    (net (code "46") (name "Net-(LED4-Pad-)") (class "Default")
      (node (ref "LED4") (pin "-") (pinfunction "-_-") (pintype "passive"))
      (node (ref "R13") (pin "1") (pinfunction "1_1") (pintype "passive"))
    )
    (net (code "47") (name "Net-(LED5-Pad-)") (class "Default")
      (node (ref "LED5") (pin "-") (pinfunction "-_-") (pintype "passive"))
      (node (ref "R14") (pin "1") (pinfunction "1_1") (pintype "passive"))
    )
    (net (code "48") (name "Net-(MEGA328_CTRL-ADC7)") (class "Default")
      (node (ref "LED5") (pin "+") (pinfunction "+_+") (pintype "passive"))
      (node (ref "MEGA328_CTRL") (pin "22") (pinfunction "ADC7_22") (pintype "bidirectional"))
    )
    (net (code "49") (name "Net-(MEGA328_CTRL-PB6(XTAL1{slash}TOSC1))") (class "Default")
      (node (ref "C39") (pin "1") (pinfunction "1_1") (pintype "passive"))
      (node (ref "MEGA328_CTRL") (pin "7") (pinfunction "PB6(XTAL1/TOSC1)_7") (pintype "bidirectional"))
      (node (ref "Y2") (pin "1") (pinfunction "1_1") (pintype "passive"))
    )
    (net (code "50") (name "Net-(MEGA328_CTRL-PB7(XTAL2{slash}TOSC2))") (class "Default")
      (node (ref "C36") (pin "1") (pinfunction "1_1") (pintype "passive"))
      (node (ref "MEGA328_CTRL") (pin "8") (pinfunction "PB7(XTAL2/TOSC2)_8") (pintype "bidirectional"))
      (node (ref "Y2") (pin "2") (pinfunction "2_2") (pintype "passive"))
    )
    (net (code "51") (name "Net-(MEGA328_OUT-PB0(ICP))") (class "Default")
      (node (ref "LED4") (pin "+") (pinfunction "+_+") (pintype "passive"))
      (node (ref "MEGA328_OUT") (pin "12") (pinfunction "PB0(ICP)_12") (pintype "bidirectional"))
    )
    (net (code "52") (name "Net-(MEGA328_OUT-PB6(XTAL1{slash}TOSC1))") (class "Default")
      (node (ref "C30") (pin "1") (pinfunction "1_1") (pintype "passive"))
      (node (ref "MEGA328_OUT") (pin "7") (pinfunction "PB6(XTAL1/TOSC1)_7") (pintype "bidirectional"))
      (node (ref "Y1") (pin "1") (pinfunction "1_1") (pintype "passive"))
    )
    (net (code "53") (name "Net-(MEGA328_OUT-PB7(XTAL2{slash}TOSC2))") (class "Default")
      (node (ref "C29") (pin "1") (pinfunction "1_1") (pintype "passive"))
      (node (ref "MEGA328_OUT") (pin "8") (pinfunction "PB7(XTAL2/TOSC2)_8") (pintype "bidirectional"))
      (node (ref "Y1") (pin "2") (pinfunction "2_2") (pintype "passive"))
    )
    (net (code "54") (name "Net-(MEGA328_OUT-PD5(T1))") (class "Default")
      (node (ref "LED1") (pin "+") (pinfunction "+_+") (pintype "passive"))
      (node (ref "MEGA328_OUT") (pin "9") (pinfunction "PD5(T1)_9") (pintype "bidirectional"))
    )
    (net (code "55") (name "Net-(MEGA328_OUT-PD6(AIN0))") (class "Default")
      (node (ref "LED2") (pin "+") (pinfunction "+_+") (pintype "passive"))
      (node (ref "MEGA328_OUT") (pin "10") (pinfunction "PD6(AIN0)_10") (pintype "bidirectional"))
    )
    (net (code "56") (name "Net-(MEGA328_OUT-PD7(AIN1))") (class "Default")
      (node (ref "LED3") (pin "+") (pinfunction "+_+") (pintype "passive"))
      (node (ref "MEGA328_OUT") (pin "11") (pinfunction "PD7(AIN1)_11") (pintype "bidirectional"))
    )
    (net (code "57") (name "Net-(TVP7002-FILT1)") (class "Default")
      (node (ref "R6") (pin "1") (pinfunction "1_1") (pintype "passive"))
      (node (ref "TVP7002") (pin "87") (pinfunction "FILT1_87") (pintype "bidirectional"))
    )
    (net (code "58") (name "Net-(TVP7002-FILT2)") (class "Default")
      (node (ref "C21") (pin "2") (pinfunction "2_2") (pintype "passive"))
      (node (ref "TVP7002") (pin "88") (pinfunction "FILT2_88") (pintype "bidirectional"))
    )
    (net (code "59") (name "Net-(TVP7002-PLL_F)") (class "Default")
      (node (ref "C21") (pin "1") (pinfunction "1_1") (pintype "passive"))
      (node (ref "C22") (pin "1") (pinfunction "1_1") (pintype "passive"))
      (node (ref "TVP7002") (pin "89") (pinfunction "PLL_F_89") (pintype "bidirectional"))
    )
    (net (code "60") (name "PCLK") (class "Default")
      (node (ref "JP4") (pin "5") (pinfunction "5_5") (pintype "passive"))
      (node (ref "TVP7002") (pin "28") (pinfunction "DATACLK_28") (pintype "bidirectional"))
    )
    (net (code "61") (name "R0") (class "Default")
      (node (ref "JP2") (pin "30") (pinfunction "30_30") (pintype "passive"))
      (node (ref "TVP7002") (pin "63") (pinfunction "R_2_63") (pintype "bidirectional"))
    )
    (net (code "62") (name "R1") (class "Default")
      (node (ref "JP2") (pin "29") (pinfunction "29_29") (pintype "passive"))
      (node (ref "TVP7002") (pin "62") (pinfunction "R_3_62") (pintype "bidirectional"))
    )
    (net (code "63") (name "R2") (class "Default")
      (node (ref "JP2") (pin "28") (pinfunction "28_28") (pintype "passive"))
      (node (ref "TVP7002") (pin "61") (pinfunction "R_4_61") (pintype "bidirectional"))
    )
    (net (code "64") (name "R3") (class "Default")
      (node (ref "JP2") (pin "27") (pinfunction "27_27") (pintype "passive"))
      (node (ref "TVP7002") (pin "59") (pinfunction "R_5_59") (pintype "bidirectional"))
    )
    (net (code "65") (name "R4") (class "Default")
      (node (ref "JP2") (pin "26") (pinfunction "26_26") (pintype "passive"))
      (node (ref "TVP7002") (pin "58") (pinfunction "R_6_58") (pintype "bidirectional"))
    )
    (net (code "66") (name "R5") (class "Default")
      (node (ref "JP2") (pin "25") (pinfunction "25_25") (pintype "passive"))
      (node (ref "TVP7002") (pin "57") (pinfunction "R_7_57") (pintype "bidirectional"))
    )
    (net (code "67") (name "R6") (class "Default")
      (node (ref "JP2") (pin "24") (pinfunction "24_24") (pintype "passive"))
      (node (ref "TVP7002") (pin "56") (pinfunction "R_8_56") (pintype "bidirectional"))
    )
    (net (code "68") (name "R7") (class "Default")
      (node (ref "JP2") (pin "23") (pinfunction "23_23") (pintype "passive"))
      (node (ref "TVP7002") (pin "55") (pinfunction "R_9_55") (pintype "bidirectional"))
    )
    (net (code "69") (name "RESET") (class "Default")
      (node (ref "I2C") (pin "3") (pinfunction "3_3") (pintype "passive"))
      (node (ref "MEGA328_CTRL") (pin "14") (pinfunction "PB2(SS/OC1B)_14") (pintype "bidirectional"))
      (node (ref "R9") (pin "2") (pinfunction "2_2") (pintype "passive"))
      (node (ref "TVP7002") (pin "71") (pinfunction "RESETB_71") (pintype "bidirectional"))
    )
    (net (code "70") (name "RIN") (class "Default")
      (node (ref "C11") (pin "1") (pinfunction "1_1") (pintype "passive"))
      (node (ref "CN1") (pin "1") (pinfunction "1_1") (pintype "bidirectional"))
      (node (ref "R4") (pin "2") (pinfunction "2_2") (pintype "passive"))
    )
    (net (code "71") (name "RIN_1") (class "Default")
      (node (ref "C11") (pin "2") (pinfunction "2_2") (pintype "passive"))
      (node (ref "TVP7002") (pin "11") (pinfunction "RIN_1_11") (pintype "bidirectional"))
    )
    (net (code "72") (name "RIN_2") (class "Default")
      (node (ref "C9") (pin "1") (pinfunction "1_1") (pintype "passive"))
      (node (ref "TVP7002") (pin "10") (pinfunction "RIN_2_10") (pintype "bidirectional"))
    )
    (net (code "73") (name "RIN_3") (class "Default")
      (node (ref "C10") (pin "1") (pinfunction "1_1") (pintype "passive"))
      (node (ref "TVP7002") (pin "9") (pinfunction "RIN_3_9") (pintype "bidirectional"))
    )
    (net (code "74") (name "SCL") (class "Default")
      (node (ref "I2C") (pin "2") (pinfunction "2_2") (pintype "passive"))
      (node (ref "MEGA328_CTRL") (pin "28") (pinfunction "PC5(ADC5/SCL)_28") (pintype "bidirectional"))
      (node (ref "R8") (pin "2") (pinfunction "2_2") (pintype "passive"))
      (node (ref "TVP7002") (pin "74") (pinfunction "SCL_74") (pintype "bidirectional"))
    )
    (net (code "75") (name "SDA") (class "Default")
      (node (ref "I2C") (pin "1") (pinfunction "1_1") (pintype "passive"))
      (node (ref "MEGA328_CTRL") (pin "27") (pinfunction "PC4(ADC4/SDA)_27") (pintype "bidirectional"))
      (node (ref "R7") (pin "2") (pinfunction "2_2") (pintype "passive"))
      (node (ref "TVP7002") (pin "75") (pinfunction "SDA_75") (pintype "bidirectional"))
    )
    (net (code "76") (name "SOGIN_1") (class "Default")
      (node (ref "C8") (pin "2") (pinfunction "2_2") (pintype "passive"))
      (node (ref "TVP7002") (pin "1") (pinfunction "SOGIN_1_1") (pintype "bidirectional"))
    )
    (net (code "77") (name "SOGIN_2") (class "Default")
      (node (ref "C17") (pin "1") (pinfunction "1_1") (pintype "passive"))
      (node (ref "TVP7002") (pin "99") (pinfunction "SOGIN_2_99") (pintype "bidirectional"))
    )
    (net (code "78") (name "SOGIN_3") (class "Default")
      (node (ref "C15") (pin "1") (pinfunction "1_1") (pintype "passive"))
      (node (ref "TVP7002") (pin "97") (pinfunction "SOGIN_3_97") (pintype "bidirectional"))
    )
    (net (code "79") (name "UNUSED1") (class "Default")
      (node (ref "JP4") (pin "17") (pinfunction "17_17") (pintype "passive"))
      (node (ref "MEGA328_OUT") (pin "30") (pinfunction "PD0(RXD)_30") (pintype "bidirectional"))
    )
    (net (code "80") (name "UNUSED2") (class "Default")
      (node (ref "JP4") (pin "15") (pinfunction "15_15") (pintype "passive"))
      (node (ref "MEGA328_OUT") (pin "31") (pinfunction "PD1(TXD)_31") (pintype "bidirectional"))
    )
    (net (code "81") (name "VSOUT") (class "Default")
      (node (ref "JP4") (pin "9") (pinfunction "9_9") (pintype "passive"))
      (node (ref "TVP7002") (pin "23") (pinfunction "VSOUT_23") (pintype "bidirectional"))
    )
    (net (code "82") (name "W_MISO") (class "Default")
      (node (ref "ISP_OUT") (pin "1") (pinfunction "1_1") (pintype "passive"))
      (node (ref "J2") (pin "7") (pinfunction "DO_7") (pintype "bidirectional"))
      (node (ref "MEGA328_OUT") (pin "16") (pinfunction "PB4(MISO)_16") (pintype "bidirectional"))
    )
    (net (code "83") (name "W_MOSI") (class "Default")
      (node (ref "ISP_OUT") (pin "4") (pinfunction "4_4") (pintype "passive"))
      (node (ref "J2") (pin "3") (pinfunction "DI_3") (pintype "bidirectional"))
      (node (ref "MEGA328_OUT") (pin "15") (pinfunction "PB3(MOSI/OC2)_15") (pintype "bidirectional"))
    )
    (net (code "84") (name "W_RST") (class "Default")
      (node (ref "ISP_OUT") (pin "5") (pinfunction "5_5") (pintype "passive"))
      (node (ref "MEGA328_OUT") (pin "29") (pinfunction "PC6(/RESET)_29") (pintype "bidirectional"))
    )
    (net (code "85") (name "W_SCK") (class "Default")
      (node (ref "ISP_OUT") (pin "3") (pinfunction "3_3") (pintype "passive"))
      (node (ref "J2") (pin "5") (pinfunction "SCLK_5") (pintype "bidirectional"))
      (node (ref "MEGA328_OUT") (pin "17") (pinfunction "PB5(SCK)_17") (pintype "bidirectional"))
    )
    (net (code "86") (name "W_VCC") (class "Default")
      (node (ref "C31") (pin "1") (pinfunction "1_1") (pintype "passive"))
      (node (ref "C32") (pin "1") (pinfunction "1_1") (pintype "passive"))
      (node (ref "C34") (pin "1") (pinfunction "1_1") (pintype "passive"))
      (node (ref "C35") (pin "1") (pinfunction "1_1") (pintype "passive"))
      (node (ref "ISP_OUT") (pin "2") (pinfunction "2_2") (pintype "passive"))
      (node (ref "J2") (pin "4") (pinfunction "VDD_4") (pintype "bidirectional"))
      (node (ref "MEGA328_OUT") (pin "18") (pinfunction "AVCC_18") (pintype "bidirectional"))
      (node (ref "MEGA328_OUT") (pin "20") (pinfunction "AREF_20") (pintype "bidirectional"))
      (node (ref "MEGA328_OUT") (pin "4") (pinfunction "VCC_4") (pintype "bidirectional"))
      (node (ref "MEGA328_OUT") (pin "6") (pinfunction "VCC_6") (pintype "bidirectional"))
      (node (ref "VREG4") (pin "2") (pinfunction "OUT_2") (pintype "output"))
      (node (ref "VREG4") (pin "4") (pinfunction "OUT_4") (pintype "output"))
    )
    (net (code "87") (name "unconnected-(27MHZ-NC-PadP1)") (class "Default")
      (node (ref "27MHZ") (pin "P1") (pinfunction "NC_P1") (pintype "bidirectional"))
    )
    (net (code "88") (name "unconnected-(J2-CDN-Pad9)") (class "Default")
      (node (ref "J2") (pin "9") (pinfunction "CDN_9") (pintype "bidirectional"))
    )
    (net (code "89") (name "unconnected-(J2-DATA1-Pad8)") (class "Default")
      (node (ref "J2") (pin "8") (pinfunction "DATA1_8") (pintype "bidirectional"))
    )
    (net (code "90") (name "unconnected-(J2-DATA2-Pad1)") (class "Default")
      (node (ref "J2") (pin "1") (pinfunction "DATA2_1") (pintype "bidirectional"))
    )
    (net (code "91") (name "unconnected-(JP2-Pad1)") (class "Default")
      (node (ref "JP2") (pin "1") (pinfunction "1_1") (pintype "passive"))
    )
    (net (code "92") (name "unconnected-(JP2-Pad3)") (class "Default")
      (node (ref "JP2") (pin "3") (pinfunction "3_3") (pintype "passive"))
    )
    (net (code "93") (name "unconnected-(JP2-Pad5)") (class "Default")
      (node (ref "JP2") (pin "5") (pinfunction "5_5") (pintype "passive"))
    )
    (net (code "94") (name "unconnected-(JP2-Pad6)") (class "Default")
      (node (ref "JP2") (pin "6") (pinfunction "6_6") (pintype "passive"))
    )
    (net (code "95") (name "unconnected-(JP2-Pad31)") (class "Default")
      (node (ref "JP2") (pin "31") (pinfunction "31_31") (pintype "passive"))
    )
    (net (code "96") (name "unconnected-(JP2-Pad32)") (class "Default")
      (node (ref "JP2") (pin "32") (pinfunction "32_32") (pintype "passive"))
    )
    (net (code "97") (name "unconnected-(JP2-Pad33)") (class "Default")
      (node (ref "JP2") (pin "33") (pinfunction "33_33") (pintype "passive"))
    )
    (net (code "98") (name "unconnected-(JP2-Pad34)") (class "Default")
      (node (ref "JP2") (pin "34") (pinfunction "34_34") (pintype "passive"))
    )
    (net (code "99") (name "unconnected-(JP2-Pad35)") (class "Default")
      (node (ref "JP2") (pin "35") (pinfunction "35_35") (pintype "passive"))
    )
    (net (code "100") (name "unconnected-(JP2-Pad36)") (class "Default")
      (node (ref "JP2") (pin "36") (pinfunction "36_36") (pintype "passive"))
    )
    (net (code "101") (name "unconnected-(JP2-Pad37)") (class "Default")
      (node (ref "JP2") (pin "37") (pinfunction "37_37") (pintype "passive"))
    )
    (net (code "102") (name "unconnected-(JP2-Pad38)") (class "Default")
      (node (ref "JP2") (pin "38") (pinfunction "38_38") (pintype "passive"))
    )
    (net (code "103") (name "unconnected-(JP2-Pad39)") (class "Default")
      (node (ref "JP2") (pin "39") (pinfunction "39_39") (pintype "passive"))
    )
    (net (code "104") (name "unconnected-(JP2-Pad40)") (class "Default")
      (node (ref "JP2") (pin "40") (pinfunction "40_40") (pintype "passive"))
    )
    (net (code "105") (name "unconnected-(JP2-Pad41)") (class "Default")
      (node (ref "JP2") (pin "41") (pinfunction "41_41") (pintype "passive"))
    )
    (net (code "106") (name "unconnected-(JP2-Pad42)") (class "Default")
      (node (ref "JP2") (pin "42") (pinfunction "42_42") (pintype "passive"))
    )
    (net (code "107") (name "unconnected-(JP2-Pad43)") (class "Default")
      (node (ref "JP2") (pin "43") (pinfunction "43_43") (pintype "passive"))
    )
    (net (code "108") (name "unconnected-(JP2-Pad44)") (class "Default")
      (node (ref "JP2") (pin "44") (pinfunction "44_44") (pintype "passive"))
    )
    (net (code "109") (name "unconnected-(JP2-Pad45)") (class "Default")
      (node (ref "JP2") (pin "45") (pinfunction "45_45") (pintype "passive"))
    )
    (net (code "110") (name "unconnected-(JP2-Pad46)") (class "Default")
      (node (ref "JP2") (pin "46") (pinfunction "46_46") (pintype "passive"))
    )
    (net (code "111") (name "unconnected-(JP2-Pad47)") (class "Default")
      (node (ref "JP2") (pin "47") (pinfunction "47_47") (pintype "passive"))
    )
    (net (code "112") (name "unconnected-(JP2-Pad48)") (class "Default")
      (node (ref "JP2") (pin "48") (pinfunction "48_48") (pintype "passive"))
    )
    (net (code "113") (name "unconnected-(JP2-Pad49)") (class "Default")
      (node (ref "JP2") (pin "49") (pinfunction "49_49") (pintype "passive"))
    )
    (net (code "114") (name "unconnected-(JP2-Pad50)") (class "Default")
      (node (ref "JP2") (pin "50") (pinfunction "50_50") (pintype "passive"))
    )
    (net (code "115") (name "unconnected-(JP4-Pad1)") (class "Default")
      (node (ref "JP4") (pin "1") (pinfunction "1_1") (pintype "passive"))
    )
    (net (code "116") (name "unconnected-(JP4-Pad2)") (class "Default")
      (node (ref "JP4") (pin "2") (pinfunction "2_2") (pintype "passive"))
    )
    (net (code "117") (name "unconnected-(JP4-Pad3)") (class "Default")
      (node (ref "JP4") (pin "3") (pinfunction "3_3") (pintype "passive"))
    )
    (net (code "118") (name "unconnected-(JP4-Pad4)") (class "Default")
      (node (ref "JP4") (pin "4") (pinfunction "4_4") (pintype "passive"))
    )
    (net (code "119") (name "unconnected-(JP4-Pad6)") (class "Default")
      (node (ref "JP4") (pin "6") (pinfunction "6_6") (pintype "passive"))
    )
    (net (code "120") (name "unconnected-(JP4-Pad8)") (class "Default")
      (node (ref "JP4") (pin "8") (pinfunction "8_8") (pintype "passive"))
    )
    (net (code "121") (name "unconnected-(JP4-Pad10)") (class "Default")
      (node (ref "JP4") (pin "10") (pinfunction "10_10") (pintype "passive"))
    )
    (net (code "122") (name "unconnected-(JP4-Pad12)") (class "Default")
      (node (ref "JP4") (pin "12") (pinfunction "12_12") (pintype "passive"))
    )
    (net (code "123") (name "unconnected-(JP4-Pad14)") (class "Default")
      (node (ref "JP4") (pin "14") (pinfunction "14_14") (pintype "passive"))
    )
    (net (code "124") (name "unconnected-(JP4-Pad16)") (class "Default")
      (node (ref "JP4") (pin "16") (pinfunction "16_16") (pintype "passive"))
    )
    (net (code "125") (name "unconnected-(JP4-Pad18)") (class "Default")
      (node (ref "JP4") (pin "18") (pinfunction "18_18") (pintype "passive"))
    )
    (net (code "126") (name "unconnected-(JP4-Pad19)") (class "Default")
      (node (ref "JP4") (pin "19") (pinfunction "19_19") (pintype "passive"))
    )
    (net (code "127") (name "unconnected-(JP4-Pad20)") (class "Default")
      (node (ref "JP4") (pin "20") (pinfunction "20_20") (pintype "passive"))
    )
    (net (code "128") (name "unconnected-(JP4-Pad21)") (class "Default")
      (node (ref "JP4") (pin "21") (pinfunction "21_21") (pintype "passive"))
    )
    (net (code "129") (name "unconnected-(JP4-Pad22)") (class "Default")
      (node (ref "JP4") (pin "22") (pinfunction "22_22") (pintype "passive"))
    )
    (net (code "130") (name "unconnected-(JP4-Pad23)") (class "Default")
      (node (ref "JP4") (pin "23") (pinfunction "23_23") (pintype "passive"))
    )
    (net (code "131") (name "unconnected-(JP4-Pad24)") (class "Default")
      (node (ref "JP4") (pin "24") (pinfunction "24_24") (pintype "passive"))
    )
    (net (code "132") (name "unconnected-(JP4-Pad25)") (class "Default")
      (node (ref "JP4") (pin "25") (pinfunction "25_25") (pintype "passive"))
    )
    (net (code "133") (name "unconnected-(JP4-Pad26)") (class "Default")
      (node (ref "JP4") (pin "26") (pinfunction "26_26") (pintype "passive"))
    )
    (net (code "134") (name "unconnected-(JP4-Pad27)") (class "Default")
      (node (ref "JP4") (pin "27") (pinfunction "27_27") (pintype "passive"))
    )
    (net (code "135") (name "unconnected-(JP4-Pad28)") (class "Default")
      (node (ref "JP4") (pin "28") (pinfunction "28_28") (pintype "passive"))
    )
    (net (code "136") (name "unconnected-(JP4-Pad29)") (class "Default")
      (node (ref "JP4") (pin "29") (pinfunction "29_29") (pintype "passive"))
    )
    (net (code "137") (name "unconnected-(JP4-Pad30)") (class "Default")
      (node (ref "JP4") (pin "30") (pinfunction "30_30") (pintype "passive"))
    )
    (net (code "138") (name "unconnected-(JP4-Pad31)") (class "Default")
      (node (ref "JP4") (pin "31") (pinfunction "31_31") (pintype "passive"))
    )
    (net (code "139") (name "unconnected-(JP4-Pad32)") (class "Default")
      (node (ref "JP4") (pin "32") (pinfunction "32_32") (pintype "passive"))
    )
    (net (code "140") (name "unconnected-(JP4-Pad33)") (class "Default")
      (node (ref "JP4") (pin "33") (pinfunction "33_33") (pintype "passive"))
    )
    (net (code "141") (name "unconnected-(JP4-Pad34)") (class "Default")
      (node (ref "JP4") (pin "34") (pinfunction "34_34") (pintype "passive"))
    )
    (net (code "142") (name "unconnected-(JP4-Pad35)") (class "Default")
      (node (ref "JP4") (pin "35") (pinfunction "35_35") (pintype "passive"))
    )
    (net (code "143") (name "unconnected-(JP4-Pad36)") (class "Default")
      (node (ref "JP4") (pin "36") (pinfunction "36_36") (pintype "passive"))
    )
    (net (code "144") (name "unconnected-(JP4-Pad37)") (class "Default")
      (node (ref "JP4") (pin "37") (pinfunction "37_37") (pintype "passive"))
    )
    (net (code "145") (name "unconnected-(JP4-Pad38)") (class "Default")
      (node (ref "JP4") (pin "38") (pinfunction "38_38") (pintype "passive"))
    )
    (net (code "146") (name "unconnected-(JP4-Pad39)") (class "Default")
      (node (ref "JP4") (pin "39") (pinfunction "39_39") (pintype "passive"))
    )
    (net (code "147") (name "unconnected-(JP4-Pad40)") (class "Default")
      (node (ref "JP4") (pin "40") (pinfunction "40_40") (pintype "passive"))
    )
    (net (code "148") (name "unconnected-(JP4-Pad41)") (class "Default")
      (node (ref "JP4") (pin "41") (pinfunction "41_41") (pintype "passive"))
    )
    (net (code "149") (name "unconnected-(JP4-Pad42)") (class "Default")
      (node (ref "JP4") (pin "42") (pinfunction "42_42") (pintype "passive"))
    )
    (net (code "150") (name "unconnected-(JP4-Pad43)") (class "Default")
      (node (ref "JP4") (pin "43") (pinfunction "43_43") (pintype "passive"))
    )
    (net (code "151") (name "unconnected-(JP4-Pad44)") (class "Default")
      (node (ref "JP4") (pin "44") (pinfunction "44_44") (pintype "passive"))
    )
    (net (code "152") (name "unconnected-(JP4-Pad45)") (class "Default")
      (node (ref "JP4") (pin "45") (pinfunction "45_45") (pintype "passive"))
    )
    (net (code "153") (name "unconnected-(JP4-Pad46)") (class "Default")
      (node (ref "JP4") (pin "46") (pinfunction "46_46") (pintype "passive"))
    )
    (net (code "154") (name "unconnected-(JP4-Pad47)") (class "Default")
      (node (ref "JP4") (pin "47") (pinfunction "47_47") (pintype "passive"))
    )
    (net (code "155") (name "unconnected-(JP4-Pad48)") (class "Default")
      (node (ref "JP4") (pin "48") (pinfunction "48_48") (pintype "passive"))
    )
    (net (code "156") (name "unconnected-(JP4-Pad49)") (class "Default")
      (node (ref "JP4") (pin "49") (pinfunction "49_49") (pintype "passive"))
    )
    (net (code "157") (name "unconnected-(JP4-Pad50)") (class "Default")
      (node (ref "JP4") (pin "50") (pinfunction "50_50") (pintype "passive"))
    )
    (net (code "158") (name "unconnected-(MEGA328_CTRL-ADC6-Pad19)") (class "Default")
      (node (ref "MEGA328_CTRL") (pin "19") (pinfunction "ADC6_19") (pintype "bidirectional"))
    )
    (net (code "159") (name "unconnected-(MEGA328_CTRL-PB0(ICP)-Pad12)") (class "Default")
      (node (ref "MEGA328_CTRL") (pin "12") (pinfunction "PB0(ICP)_12") (pintype "bidirectional"))
    )
    (net (code "160") (name "unconnected-(MEGA328_CTRL-PB1(OC1A)-Pad13)") (class "Default")
      (node (ref "MEGA328_CTRL") (pin "13") (pinfunction "PB1(OC1A)_13") (pintype "bidirectional"))
    )
    (net (code "161") (name "unconnected-(MEGA328_CTRL-PC0(ADC0)-Pad23)") (class "Default")
      (node (ref "MEGA328_CTRL") (pin "23") (pinfunction "PC0(ADC0)_23") (pintype "bidirectional"))
    )
    (net (code "162") (name "unconnected-(MEGA328_CTRL-PC1(ADC1)-Pad24)") (class "Default")
      (node (ref "MEGA328_CTRL") (pin "24") (pinfunction "PC1(ADC1)_24") (pintype "bidirectional"))
    )
    (net (code "163") (name "unconnected-(MEGA328_CTRL-PC2(ADC2)-Pad25)") (class "Default")
      (node (ref "MEGA328_CTRL") (pin "25") (pinfunction "PC2(ADC2)_25") (pintype "bidirectional"))
    )
    (net (code "164") (name "unconnected-(MEGA328_CTRL-PC3(ADC3)-Pad26)") (class "Default")
      (node (ref "MEGA328_CTRL") (pin "26") (pinfunction "PC3(ADC3)_26") (pintype "bidirectional"))
    )
    (net (code "165") (name "unconnected-(MEGA328_CTRL-PD0(RXD)-Pad30)") (class "Default")
      (node (ref "MEGA328_CTRL") (pin "30") (pinfunction "PD0(RXD)_30") (pintype "bidirectional"))
    )
    (net (code "166") (name "unconnected-(MEGA328_CTRL-PD1(TXD)-Pad31)") (class "Default")
      (node (ref "MEGA328_CTRL") (pin "31") (pinfunction "PD1(TXD)_31") (pintype "bidirectional"))
    )
    (net (code "167") (name "unconnected-(MEGA328_CTRL-PD2(INT0)-Pad32)") (class "Default")
      (node (ref "MEGA328_CTRL") (pin "32") (pinfunction "PD2(INT0)_32") (pintype "bidirectional"))
    )
    (net (code "168") (name "unconnected-(MEGA328_CTRL-PD3(INT1)-Pad1)") (class "Default")
      (node (ref "MEGA328_CTRL") (pin "1") (pinfunction "PD3(INT1)_1") (pintype "bidirectional"))
    )
    (net (code "169") (name "unconnected-(MEGA328_CTRL-PD4(XCK{slash}T0)-Pad2)") (class "Default")
      (node (ref "MEGA328_CTRL") (pin "2") (pinfunction "PD4(XCK/T0)_2") (pintype "bidirectional"))
    )
    (net (code "170") (name "unconnected-(MEGA328_CTRL-PD5(T1)-Pad9)") (class "Default")
      (node (ref "MEGA328_CTRL") (pin "9") (pinfunction "PD5(T1)_9") (pintype "bidirectional"))
    )
    (net (code "171") (name "unconnected-(MEGA328_CTRL-PD6(AIN0)-Pad10)") (class "Default")
      (node (ref "MEGA328_CTRL") (pin "10") (pinfunction "PD6(AIN0)_10") (pintype "bidirectional"))
    )
    (net (code "172") (name "unconnected-(MEGA328_CTRL-PD7(AIN1)-Pad11)") (class "Default")
      (node (ref "MEGA328_CTRL") (pin "11") (pinfunction "PD7(AIN1)_11") (pintype "bidirectional"))
    )
    (net (code "173") (name "unconnected-(MEGA328_OUT-ADC6-Pad19)") (class "Default")
      (node (ref "MEGA328_OUT") (pin "19") (pinfunction "ADC6_19") (pintype "bidirectional"))
    )
    (net (code "174") (name "unconnected-(MEGA328_OUT-ADC7-Pad22)") (class "Default")
      (node (ref "MEGA328_OUT") (pin "22") (pinfunction "ADC7_22") (pintype "bidirectional"))
    )
    (net (code "175") (name "unconnected-(MEGA328_OUT-PB1(OC1A)-Pad13)") (class "Default")
      (node (ref "MEGA328_OUT") (pin "13") (pinfunction "PB1(OC1A)_13") (pintype "bidirectional"))
    )
    (net (code "176") (name "unconnected-(MEGA328_OUT-PC0(ADC0)-Pad23)") (class "Default")
      (node (ref "MEGA328_OUT") (pin "23") (pinfunction "PC0(ADC0)_23") (pintype "bidirectional"))
    )
    (net (code "177") (name "unconnected-(MEGA328_OUT-PC1(ADC1)-Pad24)") (class "Default")
      (node (ref "MEGA328_OUT") (pin "24") (pinfunction "PC1(ADC1)_24") (pintype "bidirectional"))
    )
    (net (code "178") (name "unconnected-(MEGA328_OUT-PC2(ADC2)-Pad25)") (class "Default")
      (node (ref "MEGA328_OUT") (pin "25") (pinfunction "PC2(ADC2)_25") (pintype "bidirectional"))
    )
    (net (code "179") (name "unconnected-(MEGA328_OUT-PC3(ADC3)-Pad26)") (class "Default")
      (node (ref "MEGA328_OUT") (pin "26") (pinfunction "PC3(ADC3)_26") (pintype "bidirectional"))
    )
    (net (code "180") (name "unconnected-(MEGA328_OUT-PC4(ADC4{slash}SDA)-Pad27)") (class "Default")
      (node (ref "MEGA328_OUT") (pin "27") (pinfunction "PC4(ADC4/SDA)_27") (pintype "bidirectional"))
    )
    (net (code "181") (name "unconnected-(MEGA328_OUT-PC5(ADC5{slash}SCL)-Pad28)") (class "Default")
      (node (ref "MEGA328_OUT") (pin "28") (pinfunction "PC5(ADC5/SCL)_28") (pintype "bidirectional"))
    )
    (net (code "182") (name "unconnected-(MEGA328_OUT-PD3(INT1)-Pad1)") (class "Default")
      (node (ref "MEGA328_OUT") (pin "1") (pinfunction "PD3(INT1)_1") (pintype "bidirectional"))
    )
    (net (code "183") (name "unconnected-(MEGA328_OUT-PD4(XCK{slash}T0)-Pad2)") (class "Default")
      (node (ref "MEGA328_OUT") (pin "2") (pinfunction "PD4(XCK/T0)_2") (pintype "bidirectional"))
    )
    (net (code "184") (name "unconnected-(R12-Pad2)") (class "Default")
      (node (ref "R12") (pin "2") (pinfunction "2_2") (pintype "passive"))
    )
    (net (code "185") (name "unconnected-(TVP7002-B_0-Pad38)") (class "Default")
      (node (ref "TVP7002") (pin "38") (pinfunction "B_0_38") (pintype "bidirectional"))
    )
    (net (code "186") (name "unconnected-(TVP7002-B_1-Pad37)") (class "Default")
      (node (ref "TVP7002") (pin "37") (pinfunction "B_1_37") (pintype "bidirectional"))
    )
    (net (code "187") (name "unconnected-(TVP7002-G_0-Pad52)") (class "Default")
      (node (ref "TVP7002") (pin "52") (pinfunction "G_0_52") (pintype "bidirectional"))
    )
    (net (code "188") (name "unconnected-(TVP7002-G_1-Pad51)") (class "Default")
      (node (ref "TVP7002") (pin "51") (pinfunction "G_1_51") (pintype "bidirectional"))
    )
    (net (code "189") (name "unconnected-(TVP7002-R_0-Pad65)") (class "Default")
      (node (ref "TVP7002") (pin "65") (pinfunction "R_0_65") (pintype "bidirectional"))
    )
    (net (code "190") (name "unconnected-(TVP7002-R_1-Pad64)") (class "Default")
      (node (ref "TVP7002") (pin "64") (pinfunction "R_1_64") (pintype "bidirectional"))
    )
    (net (code "191") (name "unconnected-(TVP7002-SOGOUT-Pad25)") (class "Default")
      (node (ref "TVP7002") (pin "25") (pinfunction "SOGOUT_25") (pintype "bidirectional"))
    )
  )
)
